# H01R02.net
KiCad netlist of a schematic drawn in EAGLE
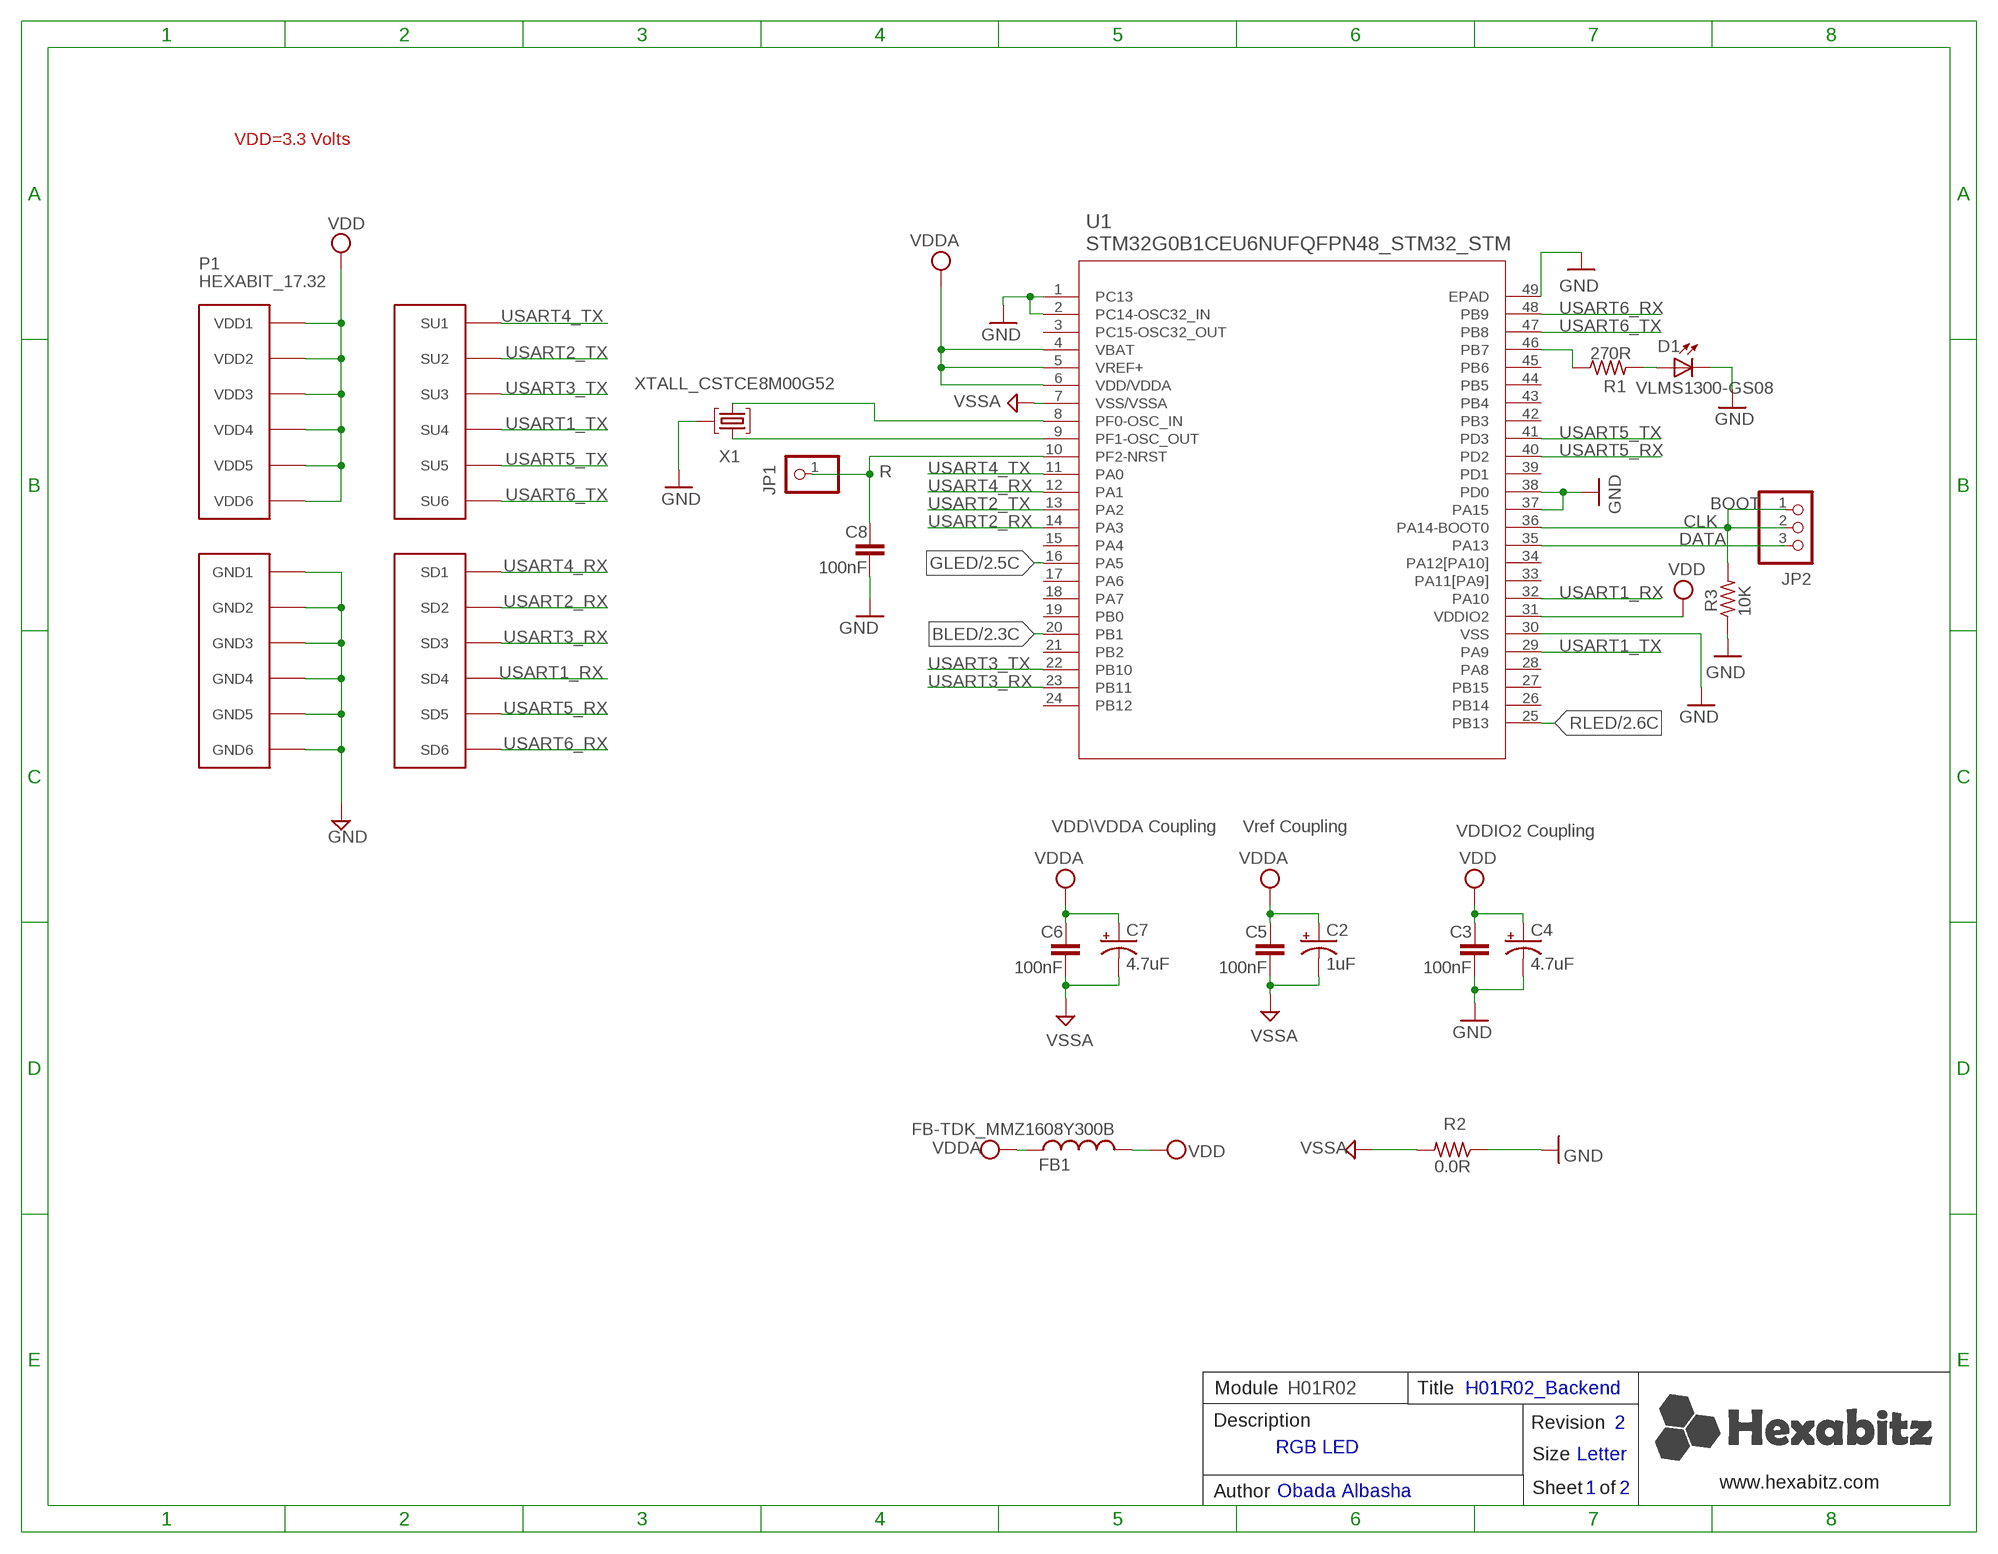
[diagram p0: schematic, sheet 1]
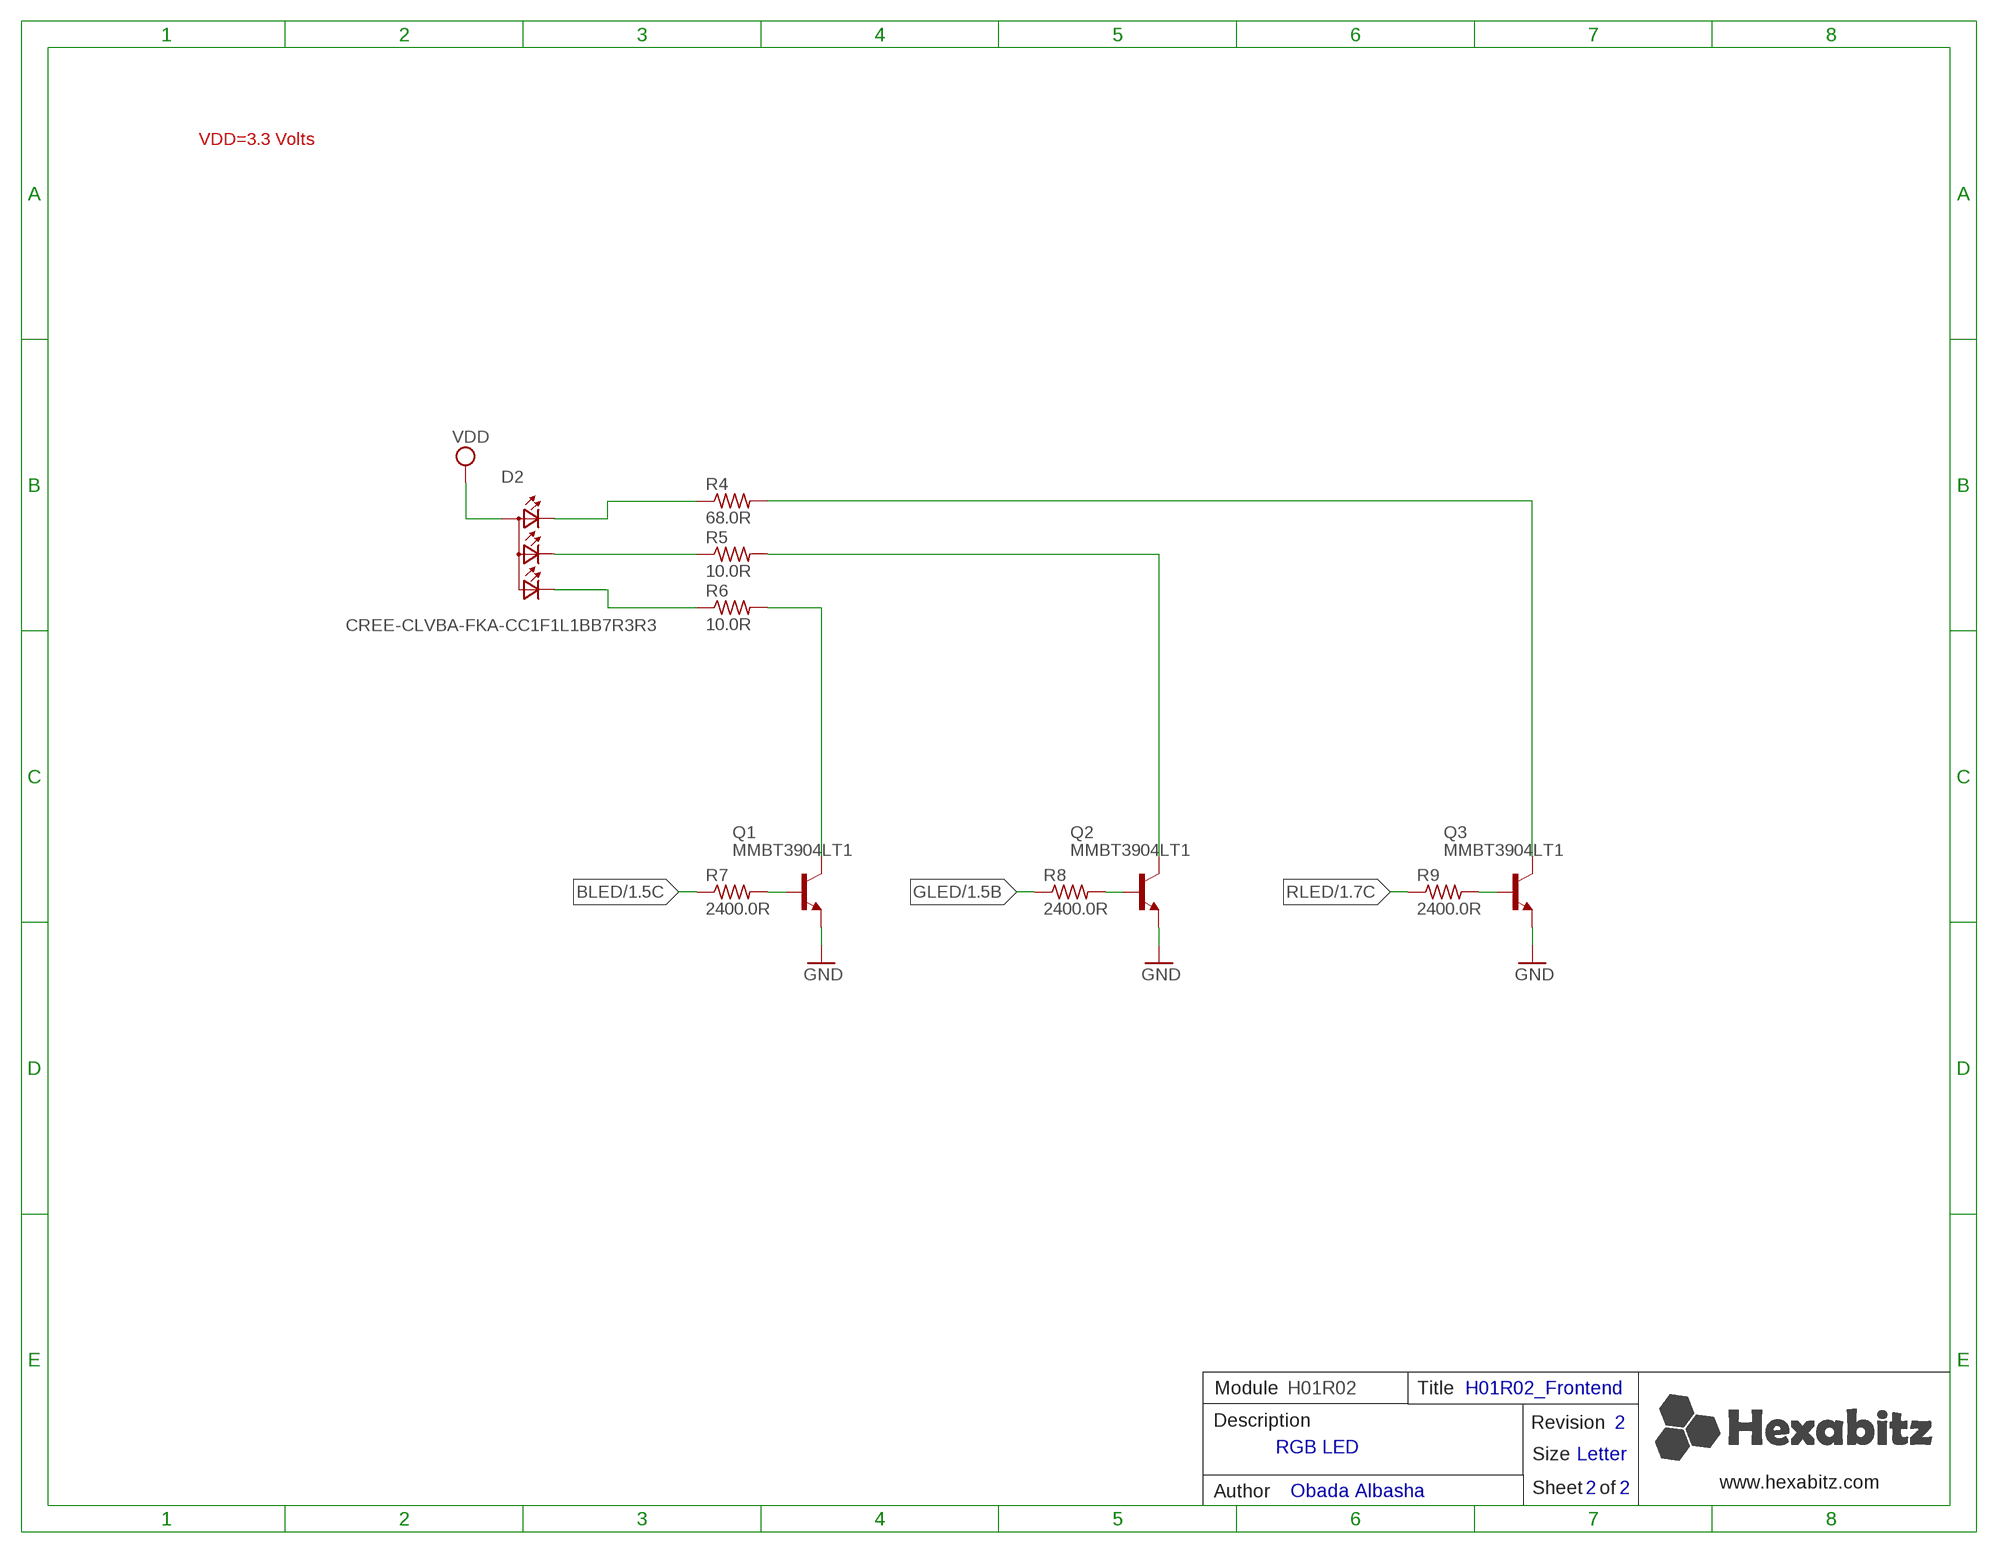
[diagram p1: schematic, sheet 2]

(export (version "E")
  (design (tool "Eeschema 10.0.6"))
  (components
    (comp (ref "C2")
      (value "1uF")
      (footprint "eagle-import:C-0805-POL")
      (libsource (lib "eagle-import") (part "C-0805-POL"))
    )
    (comp (ref "C3")
      (value "100nF")
      (footprint "eagle-import:C-0603")
      (libsource (lib "eagle-import") (part "C-0603"))
    )
    (comp (ref "C4")
      (value "4.7uF")
      (footprint "eagle-import:C-0805-POL")
      (libsource (lib "eagle-import") (part "C-0805-POL"))
    )
    (comp (ref "C5")
      (value "100nF")
      (footprint "eagle-import:C-0603")
      (libsource (lib "eagle-import") (part "C-0603"))
    )
    (comp (ref "C6")
      (value "100nF")
      (footprint "eagle-import:C-0603")
      (libsource (lib "eagle-import") (part "C-0603"))
    )
    (comp (ref "C7")
      (value "4.7uF")
      (footprint "eagle-import:C-0805-POL")
      (libsource (lib "eagle-import") (part "C-0805-POL"))
    )
    (comp (ref "C8")
      (value "100nF")
      (footprint "eagle-import:C-0603")
      (libsource (lib "eagle-import") (part "C-0603"))
    )
    (comp (ref "D1")
      (value "VLMS1300-GS08")
      (footprint "eagle-import:VLMS1300-GS08")
      (fields
        (field (name "MFN") "Vishay")
        (field (name "MPN") "VLMS1300-GS08")
        (field (name "OCTOPART_URL") "https://octopart.com/vlms1300-gs08-vishay-21709201?r=sp&s=_gcP4_q8T1SC6PJQPTQ9yA")
      )
      (libsource (lib "eagle-import") (part "VLMS1300-GS08"))
    )
    (comp (ref "FB1")
      (value "FB-TDK_MMZ1608Y300B")
      (footprint "eagle-import:FB-TDK_MMZ1608Y300B")
      (fields
        (field (name "MFN") "TDK ")
        (field (name "MPN") "MMZ1608Y300B")
        (field (name "OCTOPART_URL") "https://octopart.com/mmz1608y300b-tdk-368280?r=sp&s=cd9_2ZEqQ9q9UNBuQgHAiA")
      )
      (libsource (lib "eagle-import") (part "FB-TDK_MMZ1608Y300B"))
    )
    (comp (ref "JP1")
      (value "R")
      (footprint "eagle-import:1X01")
      (fields (field (name "MPN") "87227-1"))
      (libsource (lib "eagle-import") (part "PINHD-1X1"))
    )
    (comp (ref "JP2")
      (value "PINHD-1X3")
      (footprint "eagle-import:1X03")
      (libsource (lib "eagle-import") (part "PINHD-1X3"))
    )
    (comp (ref "P1")
      (value "HEXABIT_17.32")
      (footprint "eagle-import:HEXABIT_17.32")
      (libsource (lib "eagle-import") (part "HEXABIT_?17.32"))
    )
    (comp (ref "R1")
      (value "270R")
      (footprint "eagle-import:R-0603")
      (libsource (lib "eagle-import") (part "R-0603"))
    )
    (comp (ref "R2")
      (value "0.0R")
      (footprint "eagle-import:R-0603")
      (fields
        (field (name "MFN") "Yageo")
        (field (name "MPN") "RC0603JR-070RL")
        (field (name "OCTOPART_URL") "https://octopart.com/rc0603jr-070rl-yageo-1241539?r=sp&s=X2NteqRjRNWrnx42Y0aliA")
        (field (name "RESISTANCE") "0.0 Ohm")
      )
      (libsource (lib "eagle-import") (part "HEXABITZ_RCLS_33906182_R-0603"))
    )
    (comp (ref "R3")
      (value "10K")
      (footprint "eagle-import:R-0603")
      (libsource (lib "eagle-import") (part "R-0603"))
    )
    (comp (ref "U1")
      (value "STM32G0B1CEU6NUFQFPN48_STM32_STM")
      (footprint "eagle-import:UFQFPN48_STM32_STM")
      (fields
        (field (name "MPN") "STM32G0B1CEU6N")
        (field (name "COPYRIGHT") "Copyright (C) 2022 Ultra Librarian. All rights reserved.")
      )
      (libsource (lib "eagle-import") (part "STM32G0B1CEU6NUFQFPN48_STM32_STM"))
    )
    (comp (ref "X1")
      (value "XTALL_CSTCE8M00G52")
      (footprint "eagle-import:XTALL_CSTCE8M00G52")
      (fields (field (name "MPN") "CSTCE8M00G52Z-R0"))
      (libsource (lib "eagle-import") (part "XTALL_CSTCE8M00G52"))
    )
    (comp (ref "D2")
      (value "CREE-CLVBA-FKA-CC1F1L1BB7R3R3")
      (footprint "eagle-import:PCB-1023943-1")
      (fields (field (name "MPN") "CLVBA-FKA-CC1F1L1BB7R3R3"))
      (libsource (lib "eagle-import") (part "CREE-CLVBA-FKA-CC1F1L1BB7R3R3"))
    )
    (comp (ref "Q1")
      (value "MMBT3904LT1")
      (footprint "eagle-import:MMBT3904LT1")
      (fields
        (field (name "MFN") "ON Semiconductor")
        (field (name "MPN") "MMBT3904LT1G")
        (field (name "OCTOPART_ID") "0bb6c2bc2200d471")
        (field (name "OCTOPART_URL") "http://octopart.com/mmbt3904lt1g-on+semiconductor-3280")
        (field (name "POLARITY") "NPN")
        (field (name "POWER_DISSIPATION") "0.225W")
        (field (name "VOLTAGE_RATING_DC") "40.0V")
      )
      (libsource (lib "eagle-import") (part "MMBT3904LT1"))
    )
    (comp (ref "Q2")
      (value "MMBT3904LT1")
      (footprint "eagle-import:MMBT3904LT1")
      (fields
        (field (name "OCTOPART_ID") "0bb6c2bc2200d471")
        (field (name "OCTOPART_URL") "http://octopart.com/mmbt3904lt1g-on+semiconductor-3280")
        (field (name "POLARITY") "NPN")
        (field (name "POWER_DISSIPATION") "0.225W")
        (field (name "VOLTAGE_RATING_DC") "40.0V")
      )
      (libsource (lib "eagle-import") (part "MMBT3904LT1"))
    )
    (comp (ref "Q3")
      (value "MMBT3904LT1")
      (footprint "eagle-import:MMBT3904LT1")
      (fields
        (field (name "OCTOPART_ID") "0bb6c2bc2200d471")
        (field (name "OCTOPART_URL") "http://octopart.com/mmbt3904lt1g-on+semiconductor-3280")
        (field (name "POLARITY") "NPN")
        (field (name "POWER_DISSIPATION") "0.225W")
        (field (name "VOLTAGE_RATING_DC") "40.0V")
      )
      (libsource (lib "eagle-import") (part "MMBT3904LT1"))
    )
    (comp (ref "R4")
      (value "68.0R")
      (footprint "eagle-import:R-0603")
      (fields
        (field (name "MFN") "Vishay")
        (field (name "MPN") "CRCW060368R0FKEA")
        (field (name "OCTOPART_URL") "https://octopart.com/crcw060368r0fkea-vishay-39811903")
        (field (name "RESISTANCE") "68.0 Ω")
        (field (name "SPICEPREFIX") "R")
        (field (name "TOLERANCE") "1%")
      )
      (libsource (lib "eagle-import") (part "HEXABITZ_RCLS_33906182_R-0603"))
    )
    (comp (ref "R5")
      (value "10.0R")
      (footprint "eagle-import:R-0603")
      (fields
        (field (name "MFN") "Vishay")
        (field (name "MPN") "CRCW060310R0FKEB")
        (field (name "OCTOPART_URL") "https://octopart.com/crcw060310r0fkeb-vishay-42507905")
        (field (name "RESISTANCE") "10.0 Ω")
        (field (name "TOLERANCE") "1%")
      )
      (libsource (lib "eagle-import") (part "HEXABITZ_RCLS_33906182_R-0603"))
    )
    (comp (ref "R6")
      (value "10.0R")
      (footprint "eagle-import:R-0603")
      (fields
        (field (name "MFN") "Vishay")
        (field (name "MPN") "CRCW060310R0FKEB")
        (field (name "OCTOPART_URL") "https://octopart.com/crcw060310r0fkeb-vishay-42507905")
        (field (name "RESISTANCE") "10.0 Ω")
        (field (name "TOLERANCE") "1%")
      )
      (libsource (lib "eagle-import") (part "HEXABITZ_RCLS_33906182_R-0603"))
    )
    (comp (ref "R7")
      (value "2400.0R")
      (footprint "eagle-import:R-0603")
      (fields
        (field (name "MFN") "Vishay")
        (field (name "MPN") "CRCW06032K40JNEA")
        (field (name "OCTOPART_URL") "https://octopart.com/crcw06032k40jnea-vishay-40298967")
        (field (name "TOLERANCE") "5%")
      )
      (libsource (lib "eagle-import") (part "HEXABITZ_RCLS_33906182_R-0603"))
    )
    (comp (ref "R8")
      (value "2400.0R")
      (footprint "eagle-import:R-0603")
      (fields
        (field (name "MFN") "Vishay")
        (field (name "MPN") "CRCW06032K40JNEA")
        (field (name "OCTOPART_URL") "https://octopart.com/crcw06032k40jnea-vishay-40298967")
        (field (name "RESISTANCE") "2400.0 Ω")
        (field (name "TOLERANCE") "5%")
      )
      (libsource (lib "eagle-import") (part "HEXABITZ_RCLS_33906182_R-0603"))
    )
    (comp (ref "R9")
      (value "2400.0R")
      (footprint "eagle-import:R-0603")
      (fields
        (field (name "MFN") "Vishay")
        (field (name "MPN") "CRCW06032K40JNEA")
        (field (name "OCTOPART_URL") "https://octopart.com/crcw06032k40jnea-vishay-40298967")
        (field (name "RESISTANCE") "2400.0 Ω")
        (field (name "TOLERANCE") "5%")
      )
      (libsource (lib "eagle-import") (part "HEXABITZ_RCLS_33906182_R-0603"))
    )
  )
  (nets
    (net (code "1") (name "BLED") (class "Default")
      (node (ref "R7") (pin "1") (pinfunction "1_1") (pintype "passive"))
      (node (ref "U1") (pin "20") (pinfunction "PB1_20") (pintype "bidirectional"))
    )
    (net (code "2") (name "CLK") (class "Default")
      (node (ref "JP2") (pin "1") (pinfunction "1_1") (pintype "passive"))
      (node (ref "JP2") (pin "2") (pinfunction "2_2") (pintype "passive"))
      (node (ref "R3") (pin "2") (pinfunction "2_2") (pintype "passive"))
      (node (ref "U1") (pin "36") (pinfunction "PA14-BOOT0_36") (pintype "bidirectional"))
    )
    (net (code "3") (name "DATA") (class "Default")
      (node (ref "JP2") (pin "3") (pinfunction "3_3") (pintype "passive"))
      (node (ref "U1") (pin "35") (pinfunction "PA13_35") (pintype "bidirectional"))
    )
    (net (code "4") (name "GLED") (class "Default")
      (node (ref "R8") (pin "1") (pinfunction "1_1") (pintype "passive"))
      (node (ref "U1") (pin "16") (pinfunction "PA5_16") (pintype "bidirectional"))
    )
    (net (code "5") (name "GND") (class "Default")
      (node (ref "C3") (pin "2") (pinfunction "2_2") (pintype "passive"))
      (node (ref "C4") (pin "2") (pinfunction "-_2") (pintype "passive"))
      (node (ref "C8") (pin "2") (pinfunction "2_2") (pintype "passive"))
      (node (ref "D1") (pin "C") (pinfunction "C_C") (pintype "passive"))
      (node (ref "P1") (pin "PAD_PD10") (pinfunction "GND4_PAD_PD10") (pintype "power_in"))
      (node (ref "P1") (pin "PAD_PD11") (pinfunction "GND5_PAD_PD11") (pintype "power_in"))
      (node (ref "P1") (pin "PAD_PD12") (pinfunction "GND6_PAD_PD12") (pintype "power_in"))
      (node (ref "P1") (pin "PAD_PD7") (pinfunction "GND1_PAD_PD7") (pintype "power_in"))
      (node (ref "P1") (pin "PAD_PD8") (pinfunction "GND2_PAD_PD8") (pintype "power_in"))
      (node (ref "P1") (pin "PAD_PD9") (pinfunction "GND3_PAD_PD9") (pintype "power_in"))
      (node (ref "Q1") (pin "2") (pinfunction "E_2") (pintype "passive"))
      (node (ref "Q2") (pin "2") (pinfunction "E_2") (pintype "passive"))
      (node (ref "Q3") (pin "2") (pinfunction "E_2") (pintype "passive"))
      (node (ref "R2") (pin "1") (pinfunction "1_1") (pintype "passive"))
      (node (ref "R3") (pin "1") (pinfunction "1_1") (pintype "passive"))
      (node (ref "U1") (pin "1") (pinfunction "PC13_1") (pintype "bidirectional"))
      (node (ref "U1") (pin "2") (pinfunction "PC14-OSC32_IN_2") (pintype "bidirectional"))
      (node (ref "U1") (pin "30") (pinfunction "VSS_30") (pintype "passive"))
      (node (ref "U1") (pin "37") (pinfunction "PA15_37") (pintype "bidirectional"))
      (node (ref "U1") (pin "38") (pinfunction "PD0_38") (pintype "bidirectional"))
      (node (ref "U1") (pin "49") (pinfunction "EPAD_49") (pintype "passive"))
      (node (ref "X1") (pin "P$2") (pinfunction "2_P$2") (pintype "passive"))
    )
    (net (code "6") (name "Net-(D1-PadA)") (class "Default")
      (node (ref "D1") (pin "A") (pinfunction "A_A") (pintype "passive"))
      (node (ref "R1") (pin "2") (pinfunction "2_2") (pintype "passive"))
    )
    (net (code "7") (name "Net-(D2-CBLUE)") (class "Default")
      (node (ref "D2") (pin "P$3") (pinfunction "CBLUE_P$3") (pintype "passive"))
      (node (ref "R6") (pin "1") (pinfunction "1_1") (pintype "passive"))
    )
    (net (code "8") (name "Net-(D2-CGREEN)") (class "Default")
      (node (ref "D2") (pin "P$4") (pinfunction "CGREEN_P$4") (pintype "passive"))
      (node (ref "R5") (pin "1") (pinfunction "1_1") (pintype "passive"))
    )
    (net (code "9") (name "Net-(D2-CRED)") (class "Default")
      (node (ref "D2") (pin "P$1") (pinfunction "CRED_P$1") (pintype "passive"))
      (node (ref "R4") (pin "1") (pinfunction "1_1") (pintype "passive"))
    )
    (net (code "10") (name "Net-(Q1-B)") (class "Default")
      (node (ref "Q1") (pin "1") (pinfunction "B_1") (pintype "passive"))
      (node (ref "R7") (pin "2") (pinfunction "2_2") (pintype "passive"))
    )
    (net (code "11") (name "Net-(Q1-C)") (class "Default")
      (node (ref "Q1") (pin "3") (pinfunction "C_3") (pintype "passive"))
      (node (ref "R6") (pin "2") (pinfunction "2_2") (pintype "passive"))
    )
    (net (code "12") (name "Net-(Q2-B)") (class "Default")
      (node (ref "Q2") (pin "1") (pinfunction "B_1") (pintype "passive"))
      (node (ref "R8") (pin "2") (pinfunction "2_2") (pintype "passive"))
    )
    (net (code "13") (name "Net-(Q2-C)") (class "Default")
      (node (ref "Q2") (pin "3") (pinfunction "C_3") (pintype "passive"))
      (node (ref "R5") (pin "2") (pinfunction "2_2") (pintype "passive"))
    )
    (net (code "14") (name "Net-(Q3-B)") (class "Default")
      (node (ref "Q3") (pin "1") (pinfunction "B_1") (pintype "passive"))
      (node (ref "R9") (pin "2") (pinfunction "2_2") (pintype "passive"))
    )
    (net (code "15") (name "Net-(Q3-C)") (class "Default")
      (node (ref "Q3") (pin "3") (pinfunction "C_3") (pintype "passive"))
      (node (ref "R4") (pin "2") (pinfunction "2_2") (pintype "passive"))
    )
    (net (code "16") (name "Net-(U1-PB7)") (class "Default")
      (node (ref "R1") (pin "1") (pinfunction "1_1") (pintype "passive"))
      (node (ref "U1") (pin "46") (pinfunction "PB7_46") (pintype "bidirectional"))
    )
    (net (code "17") (name "Net-(U1-PF0-OSC_IN)") (class "Default")
      (node (ref "U1") (pin "8") (pinfunction "PF0-OSC_IN_8") (pintype "bidirectional"))
      (node (ref "X1") (pin "P$3") (pinfunction "3_P$3") (pintype "passive"))
    )
    (net (code "18") (name "Net-(U1-PF1-OSC_OUT)") (class "Default")
      (node (ref "U1") (pin "9") (pinfunction "PF1-OSC_OUT_9") (pintype "bidirectional"))
      (node (ref "X1") (pin "P$1") (pinfunction "1_P$1") (pintype "passive"))
    )
    (net (code "19") (name "Net-(U1-PF2-NRST)") (class "Default")
      (node (ref "C8") (pin "1") (pinfunction "1_1") (pintype "passive"))
      (node (ref "JP1") (pin "1") (pinfunction "1_1") (pintype "passive"))
      (node (ref "U1") (pin "10") (pinfunction "PF2-NRST_10") (pintype "bidirectional"))
    )
    (net (code "20") (name "RLED") (class "Default")
      (node (ref "R9") (pin "1") (pinfunction "1_1") (pintype "passive"))
      (node (ref "U1") (pin "25") (pinfunction "PB13_25") (pintype "bidirectional"))
    )
    (net (code "21") (name "USART1_RX") (class "Default")
      (node (ref "P1") (pin "PAD_PD4") (pinfunction "SD4_PAD_PD4") (pintype "bidirectional"))
      (node (ref "U1") (pin "32") (pinfunction "PA10_32") (pintype "bidirectional"))
    )
    (net (code "22") (name "USART1_TX") (class "Default")
      (node (ref "P1") (pin "PAD_PU4") (pinfunction "SU4_PAD_PU4") (pintype "bidirectional"))
      (node (ref "U1") (pin "29") (pinfunction "PA9_29") (pintype "bidirectional"))
    )
    (net (code "23") (name "USART2_RX") (class "Default")
      (node (ref "P1") (pin "PAD_PD2") (pinfunction "SD2_PAD_PD2") (pintype "bidirectional"))
      (node (ref "U1") (pin "14") (pinfunction "PA3_14") (pintype "bidirectional"))
    )
    (net (code "24") (name "USART2_TX") (class "Default")
      (node (ref "P1") (pin "PAD_PU2") (pinfunction "SU2_PAD_PU2") (pintype "bidirectional"))
      (node (ref "U1") (pin "13") (pinfunction "PA2_13") (pintype "bidirectional"))
    )
    (net (code "25") (name "USART3_RX") (class "Default")
      (node (ref "P1") (pin "PAD_PD3") (pinfunction "SD3_PAD_PD3") (pintype "bidirectional"))
      (node (ref "U1") (pin "23") (pinfunction "PB11_23") (pintype "bidirectional"))
    )
    (net (code "26") (name "USART3_TX") (class "Default")
      (node (ref "P1") (pin "PAD_PU3") (pinfunction "SU3_PAD_PU3") (pintype "bidirectional"))
      (node (ref "U1") (pin "22") (pinfunction "PB10_22") (pintype "bidirectional"))
    )
    (net (code "27") (name "USART4_RX") (class "Default")
      (node (ref "P1") (pin "PAD_PD1") (pinfunction "SD1_PAD_PD1") (pintype "bidirectional"))
      (node (ref "U1") (pin "12") (pinfunction "PA1_12") (pintype "bidirectional"))
    )
    (net (code "28") (name "USART4_TX") (class "Default")
      (node (ref "P1") (pin "PAD_PU1") (pinfunction "SU1_PAD_PU1") (pintype "bidirectional"))
      (node (ref "U1") (pin "11") (pinfunction "PA0_11") (pintype "bidirectional"))
    )
    (net (code "29") (name "USART5_RX") (class "Default")
      (node (ref "P1") (pin "PAD_PD5") (pinfunction "SD5_PAD_PD5") (pintype "bidirectional"))
      (node (ref "U1") (pin "40") (pinfunction "PD2_40") (pintype "bidirectional"))
    )
    (net (code "30") (name "USART5_TX") (class "Default")
      (node (ref "P1") (pin "PAD_PU5") (pinfunction "SU5_PAD_PU5") (pintype "bidirectional"))
      (node (ref "U1") (pin "41") (pinfunction "PD3_41") (pintype "bidirectional"))
    )
    (net (code "31") (name "USART6_RX") (class "Default")
      (node (ref "P1") (pin "PAD_PD6") (pinfunction "SD6_PAD_PD6") (pintype "bidirectional"))
      (node (ref "U1") (pin "48") (pinfunction "PB9_48") (pintype "bidirectional"))
    )
    (net (code "32") (name "USART6_TX") (class "Default")
      (node (ref "P1") (pin "PAD_PU6") (pinfunction "SU6_PAD_PU6") (pintype "bidirectional"))
      (node (ref "U1") (pin "47") (pinfunction "PB8_47") (pintype "bidirectional"))
    )
    (net (code "33") (name "VDD") (class "Default")
      (node (ref "C3") (pin "1") (pinfunction "1_1") (pintype "passive"))
      (node (ref "C4") (pin "1") (pinfunction "+_1") (pintype "passive"))
      (node (ref "D2") (pin "P$2") (pinfunction "A2_P$2") (pintype "passive"))
      (node (ref "FB1") (pin "2") (pinfunction "2_2") (pintype "passive"))
      (node (ref "P1") (pin "PAD_PU10") (pinfunction "VDD4_PAD_PU10") (pintype "power_in"))
      (node (ref "P1") (pin "PAD_PU11") (pinfunction "VDD5_PAD_PU11") (pintype "power_in"))
      (node (ref "P1") (pin "PAD_PU12") (pinfunction "VDD6_PAD_PU12") (pintype "power_in"))
      (node (ref "P1") (pin "PAD_PU7") (pinfunction "VDD1_PAD_PU7") (pintype "power_in"))
      (node (ref "P1") (pin "PAD_PU8") (pinfunction "VDD2_PAD_PU8") (pintype "power_in"))
      (node (ref "P1") (pin "PAD_PU9") (pinfunction "VDD3_PAD_PU9") (pintype "power_in"))
      (node (ref "U1") (pin "31") (pinfunction "VDDIO2_31") (pintype "power_in"))
    )
    (net (code "34") (name "VDDA") (class "Default")
      (node (ref "C2") (pin "1") (pinfunction "+_1") (pintype "passive"))
      (node (ref "C5") (pin "1") (pinfunction "1_1") (pintype "passive"))
      (node (ref "C6") (pin "1") (pinfunction "1_1") (pintype "passive"))
      (node (ref "C7") (pin "1") (pinfunction "+_1") (pintype "passive"))
      (node (ref "FB1") (pin "1") (pinfunction "1_1") (pintype "passive"))
      (node (ref "U1") (pin "4") (pinfunction "VBAT_4") (pintype "power_in"))
      (node (ref "U1") (pin "5") (pinfunction "VREF+_5") (pintype "power_in"))
      (node (ref "U1") (pin "6") (pinfunction "VDD/VDDA_6") (pintype "power_in"))
    )
    (net (code "35") (name "VSSA") (class "Default")
      (node (ref "C2") (pin "2") (pinfunction "-_2") (pintype "passive"))
      (node (ref "C5") (pin "2") (pinfunction "2_2") (pintype "passive"))
      (node (ref "C6") (pin "2") (pinfunction "2_2") (pintype "passive"))
      (node (ref "C7") (pin "2") (pinfunction "-_2") (pintype "passive"))
      (node (ref "R2") (pin "2") (pinfunction "2_2") (pintype "passive"))
      (node (ref "U1") (pin "7") (pinfunction "VSS/VSSA_7") (pintype "passive"))
    )
    (net (code "36") (name "unconnected-(U1-PA4-Pad15)") (class "Default")
      (node (ref "U1") (pin "15") (pinfunction "PA4_15") (pintype "bidirectional"))
    )
    (net (code "37") (name "unconnected-(U1-PA6-Pad17)") (class "Default")
      (node (ref "U1") (pin "17") (pinfunction "PA6_17") (pintype "bidirectional"))
    )
    (net (code "38") (name "unconnected-(U1-PA7-Pad18)") (class "Default")
      (node (ref "U1") (pin "18") (pinfunction "PA7_18") (pintype "bidirectional"))
    )
    (net (code "39") (name "unconnected-(U1-PA8-Pad28)") (class "Default")
      (node (ref "U1") (pin "28") (pinfunction "PA8_28") (pintype "bidirectional"))
    )
    (net (code "40") (name "unconnected-(U1-PA11[PA9]-Pad33)") (class "Default")
      (node (ref "U1") (pin "33") (pinfunction "PA11[PA9]_33") (pintype "bidirectional"))
    )
    (net (code "41") (name "unconnected-(U1-PA12[PA10]-Pad34)") (class "Default")
      (node (ref "U1") (pin "34") (pinfunction "PA12[PA10]_34") (pintype "bidirectional"))
    )
    (net (code "42") (name "unconnected-(U1-PB0-Pad19)") (class "Default")
      (node (ref "U1") (pin "19") (pinfunction "PB0_19") (pintype "bidirectional"))
    )
    (net (code "43") (name "unconnected-(U1-PB2-Pad21)") (class "Default")
      (node (ref "U1") (pin "21") (pinfunction "PB2_21") (pintype "bidirectional"))
    )
    (net (code "44") (name "unconnected-(U1-PB3-Pad42)") (class "Default")
      (node (ref "U1") (pin "42") (pinfunction "PB3_42") (pintype "bidirectional"))
    )
    (net (code "45") (name "unconnected-(U1-PB4-Pad43)") (class "Default")
      (node (ref "U1") (pin "43") (pinfunction "PB4_43") (pintype "bidirectional"))
    )
    (net (code "46") (name "unconnected-(U1-PB5-Pad44)") (class "Default")
      (node (ref "U1") (pin "44") (pinfunction "PB5_44") (pintype "bidirectional"))
    )
    (net (code "47") (name "unconnected-(U1-PB6-Pad45)") (class "Default")
      (node (ref "U1") (pin "45") (pinfunction "PB6_45") (pintype "bidirectional"))
    )
    (net (code "48") (name "unconnected-(U1-PB12-Pad24)") (class "Default")
      (node (ref "U1") (pin "24") (pinfunction "PB12_24") (pintype "bidirectional"))
    )
    (net (code "49") (name "unconnected-(U1-PB14-Pad26)") (class "Default")
      (node (ref "U1") (pin "26") (pinfunction "PB14_26") (pintype "bidirectional"))
    )
    (net (code "50") (name "unconnected-(U1-PB15-Pad27)") (class "Default")
      (node (ref "U1") (pin "27") (pinfunction "PB15_27") (pintype "bidirectional"))
    )
    (net (code "51") (name "unconnected-(U1-PC15-OSC32_OUT-Pad3)") (class "Default")
      (node (ref "U1") (pin "3") (pinfunction "PC15-OSC32_OUT_3") (pintype "bidirectional"))
    )
    (net (code "52") (name "unconnected-(U1-PD1-Pad39)") (class "Default")
      (node (ref "U1") (pin "39") (pinfunction "PD1_39") (pintype "bidirectional"))
    )
  )
)
